# lab8Edit2.net
KiCad netlist of a schematic drawn in EAGLE
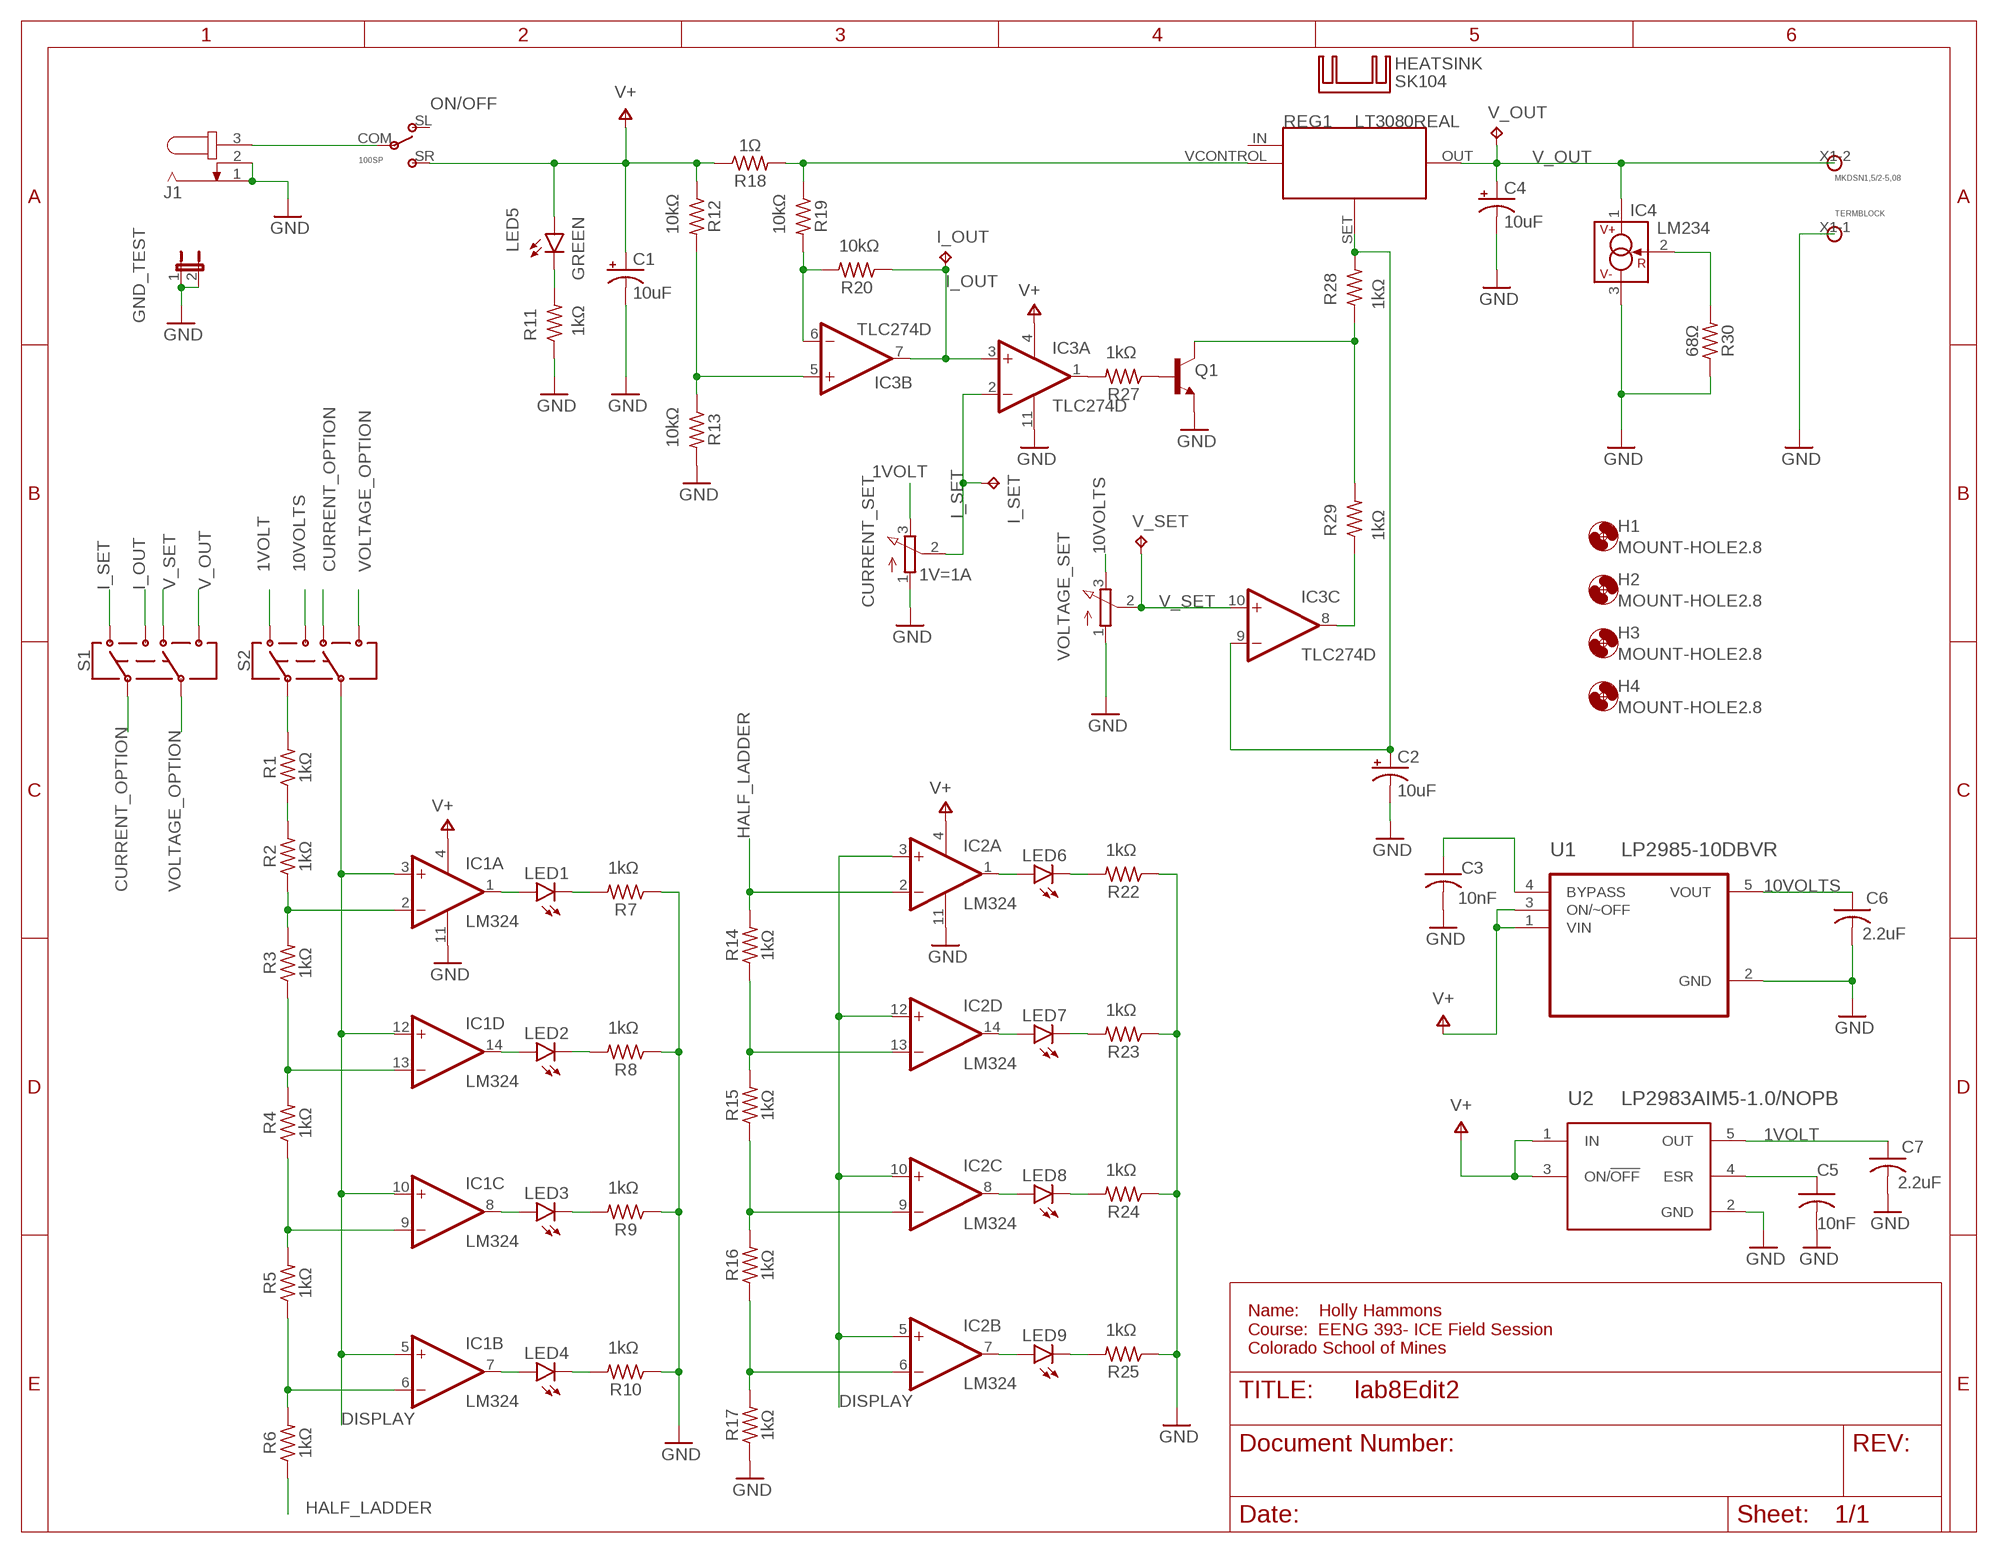
[diagram p0: schematic, sheet 1]

(export (version "E")
  (design (tool "Eeschema 10.0.6"))
  (components
    (comp (ref "C1")
      (value "10uF")
      (footprint "eagle-import:PANASONIC_B")
      (libsource (lib "eagle-import") (part "CPOL-USB"))
    )
    (comp (ref "C2")
      (value "10uF")
      (footprint "eagle-import:PANASONIC_B")
      (libsource (lib "eagle-import") (part "CPOL-USB"))
    )
    (comp (ref "C3")
      (value "10nF")
      (footprint "eagle-import:C1206")
      (libsource (lib "eagle-import") (part "C-USC1206"))
    )
    (comp (ref "C4")
      (value "10uF")
      (footprint "eagle-import:PANASONIC_B")
      (libsource (lib "eagle-import") (part "CPOL-USB"))
    )
    (comp (ref "C5")
      (value "10nF")
      (footprint "eagle-import:C1206")
      (libsource (lib "eagle-import") (part "C-USC1206"))
    )
    (comp (ref "C6")
      (value "2.2uF")
      (footprint "eagle-import:C1206")
      (libsource (lib "eagle-import") (part "C-USC1206"))
    )
    (comp (ref "C7")
      (value "2.2uF")
      (footprint "eagle-import:C1206")
      (libsource (lib "eagle-import") (part "C-USC1206"))
    )
    (comp (ref "CURRENT_SET")
      (value "1V=1A")
      (footprint "eagle-import:EVUF")
      (libsource (lib "eagle-import") (part "EVUAF2"))
    )
    (comp (ref "GND_TEST")
      (value "JP1E")
      (footprint "eagle-import:JP1")
      (libsource (lib "eagle-import") (part "JP1E"))
    )
    (comp (ref "H1")
      (value "MOUNT-HOLE2.8")
      (footprint "eagle-import:2,8")
      (libsource (lib "eagle-import") (part "MOUNT-HOLE2.8"))
    )
    (comp (ref "H2")
      (value "MOUNT-HOLE2.8")
      (footprint "eagle-import:2,8")
      (libsource (lib "eagle-import") (part "MOUNT-HOLE2.8"))
    )
    (comp (ref "H3")
      (value "MOUNT-HOLE2.8")
      (footprint "eagle-import:2,8")
      (libsource (lib "eagle-import") (part "MOUNT-HOLE2.8"))
    )
    (comp (ref "H4")
      (value "MOUNT-HOLE2.8")
      (footprint "eagle-import:2,8")
      (libsource (lib "eagle-import") (part "MOUNT-HOLE2.8"))
    )
    (comp (ref "HEATSINK")
      (value "SK104")
      (footprint "eagle-import:SK104")
      (libsource (lib "eagle-import") (part "SK104"))
    )
    (comp (ref "IC1")
      (value "LM324")
      (footprint "eagle-import:SO14")
      (libsource (lib "eagle-import") (part "LM324D"))
    )
    (comp (ref "IC2")
      (value "LM324")
      (footprint "eagle-import:SO14")
      (libsource (lib "eagle-import") (part "LM324D"))
    )
    (comp (ref "IC3")
      (value "TLC274D")
      (footprint "eagle-import:SO14")
      (libsource (lib "eagle-import") (part "TLC274D"))
    )
    (comp (ref "IC4")
      (value "LM234")
      (footprint "eagle-import:TO92")
      (libsource (lib "eagle-import") (part "LM34Z3"))
    )
    (comp (ref "I_OUT")
      (value "TPPAD1-13")
      (footprint "eagle-import:P1-13")
      (libsource (lib "eagle-import") (part "TPPAD1-13"))
    )
    (comp (ref "I_SET")
      (value "TPPAD1-13")
      (footprint "eagle-import:P1-13")
      (libsource (lib "eagle-import") (part "TPPAD1-13"))
    )
    (comp (ref "J1")
      (value "JACK-PLUG0")
      (footprint "eagle-import:SPC4077")
      (libsource (lib "eagle-import") (part "JACK-PLUG0"))
    )
    (comp (ref "LED1")
      (value "LEDCHIPLED_1206")
      (footprint "eagle-import:CHIPLED_1206")
      (libsource (lib "eagle-import") (part "LEDCHIPLED_1206"))
    )
    (comp (ref "LED2")
      (value "LEDCHIPLED_1206")
      (footprint "eagle-import:CHIPLED_1206")
      (libsource (lib "eagle-import") (part "LEDCHIPLED_1206"))
    )
    (comp (ref "LED3")
      (value "LEDCHIPLED_1206")
      (footprint "eagle-import:CHIPLED_1206")
      (libsource (lib "eagle-import") (part "LEDCHIPLED_1206"))
    )
    (comp (ref "LED4")
      (value "LEDCHIPLED_1206")
      (footprint "eagle-import:CHIPLED_1206")
      (libsource (lib "eagle-import") (part "LEDCHIPLED_1206"))
    )
    (comp (ref "LED5")
      (value "GREEN")
      (footprint "eagle-import:CHIPLED_1206")
      (libsource (lib "eagle-import") (part "LEDCHIPLED_1206"))
    )
    (comp (ref "LED6")
      (value "LEDCHIPLED_1206")
      (footprint "eagle-import:CHIPLED_1206")
      (libsource (lib "eagle-import") (part "LEDCHIPLED_1206"))
    )
    (comp (ref "LED7")
      (value "LEDCHIPLED_1206")
      (footprint "eagle-import:CHIPLED_1206")
      (libsource (lib "eagle-import") (part "LEDCHIPLED_1206"))
    )
    (comp (ref "LED8")
      (value "LEDCHIPLED_1206")
      (footprint "eagle-import:CHIPLED_1206")
      (libsource (lib "eagle-import") (part "LEDCHIPLED_1206"))
    )
    (comp (ref "LED9")
      (value "LEDCHIPLED_1206")
      (footprint "eagle-import:CHIPLED_1206")
      (libsource (lib "eagle-import") (part "LEDCHIPLED_1206"))
    )
    (comp (ref "MKDSN1,5/2-5,08")
      (value "TERMBLOCK")
      (footprint "eagle-import:TERMBLOCK")
      (libsource (lib "eagle-import") (part "TERMBLOCK"))
    )
    (comp (ref "ON/OFF")
      (value "100SP")
      (footprint "eagle-import:SP100")
      (libsource (lib "eagle-import") (part "100SP"))
    )
    (comp (ref "Q1")
      (value "TRANS_NPN-MMBTA42")
      (footprint "eagle-import:SOT23-3")
      (libsource (lib "eagle-import") (part "TRANS_NPN-MMBTA42"))
    )
    (comp (ref "R1")
      (value "1kΩ")
      (footprint "eagle-import:R1206")
      (libsource (lib "eagle-import") (part "R-US_R1206"))
    )
    (comp (ref "R2")
      (value "1kΩ")
      (footprint "eagle-import:R1206")
      (libsource (lib "eagle-import") (part "R-US_R1206"))
    )
    (comp (ref "R3")
      (value "1kΩ")
      (footprint "eagle-import:R1206")
      (libsource (lib "eagle-import") (part "R-US_R1206"))
    )
    (comp (ref "R4")
      (value "1kΩ")
      (footprint "eagle-import:R1206")
      (libsource (lib "eagle-import") (part "R-US_R1206"))
    )
    (comp (ref "R5")
      (value "1kΩ")
      (footprint "eagle-import:R1206")
      (libsource (lib "eagle-import") (part "R-US_R1206"))
    )
    (comp (ref "R6")
      (value "1kΩ")
      (footprint "eagle-import:R1206")
      (libsource (lib "eagle-import") (part "R-US_R1206"))
    )
    (comp (ref "R7")
      (value "1kΩ")
      (footprint "eagle-import:R1206")
      (libsource (lib "eagle-import") (part "R-US_R1206"))
    )
    (comp (ref "R8")
      (value "1kΩ")
      (footprint "eagle-import:R1206")
      (libsource (lib "eagle-import") (part "R-US_R1206"))
    )
    (comp (ref "R9")
      (value "1kΩ")
      (footprint "eagle-import:R1206")
      (libsource (lib "eagle-import") (part "R-US_R1206"))
    )
    (comp (ref "R10")
      (value "1kΩ")
      (footprint "eagle-import:R1206")
      (libsource (lib "eagle-import") (part "R-US_R1206"))
    )
    (comp (ref "R11")
      (value "1kΩ")
      (footprint "eagle-import:R1206")
      (libsource (lib "eagle-import") (part "R-US_R1206"))
    )
    (comp (ref "R12")
      (value "10kΩ")
      (footprint "eagle-import:R1206")
      (libsource (lib "eagle-import") (part "R-US_R1206"))
    )
    (comp (ref "R13")
      (value "10kΩ")
      (footprint "eagle-import:R1206")
      (libsource (lib "eagle-import") (part "R-US_R1206"))
    )
    (comp (ref "R14")
      (value "1kΩ")
      (footprint "eagle-import:R1206")
      (libsource (lib "eagle-import") (part "R-US_R1206"))
    )
    (comp (ref "R15")
      (value "1kΩ")
      (footprint "eagle-import:R1206")
      (libsource (lib "eagle-import") (part "R-US_R1206"))
    )
    (comp (ref "R16")
      (value "1kΩ")
      (footprint "eagle-import:R1206")
      (libsource (lib "eagle-import") (part "R-US_R1206"))
    )
    (comp (ref "R17")
      (value "1kΩ")
      (footprint "eagle-import:R1206")
      (libsource (lib "eagle-import") (part "R-US_R1206"))
    )
    (comp (ref "R18")
      (value "1Ω")
      (footprint "eagle-import:0411_15")
      (libsource (lib "eagle-import") (part "R-US_0411/15"))
    )
    (comp (ref "R19")
      (value "10kΩ")
      (footprint "eagle-import:R1206")
      (libsource (lib "eagle-import") (part "R-US_R1206"))
    )
    (comp (ref "R20")
      (value "10kΩ")
      (footprint "eagle-import:R1206")
      (libsource (lib "eagle-import") (part "R-US_R1206"))
    )
    (comp (ref "R22")
      (value "1kΩ")
      (footprint "eagle-import:R1206")
      (libsource (lib "eagle-import") (part "R-US_R1206"))
    )
    (comp (ref "R23")
      (value "1kΩ")
      (footprint "eagle-import:R1206")
      (libsource (lib "eagle-import") (part "R-US_R1206"))
    )
    (comp (ref "R24")
      (value "1kΩ")
      (footprint "eagle-import:R1206")
      (libsource (lib "eagle-import") (part "R-US_R1206"))
    )
    (comp (ref "R25")
      (value "1kΩ")
      (footprint "eagle-import:R1206")
      (libsource (lib "eagle-import") (part "R-US_R1206"))
    )
    (comp (ref "R27")
      (value "1kΩ")
      (footprint "eagle-import:R1206")
      (libsource (lib "eagle-import") (part "R-US_R1206"))
    )
    (comp (ref "R28")
      (value "1kΩ")
      (footprint "eagle-import:R1206")
      (libsource (lib "eagle-import") (part "R-US_R1206"))
    )
    (comp (ref "R29")
      (value "1kΩ")
      (footprint "eagle-import:R1206")
      (libsource (lib "eagle-import") (part "R-US_R1206"))
    )
    (comp (ref "R30")
      (value "68Ω")
      (footprint "eagle-import:R1206")
      (libsource (lib "eagle-import") (part "R-US_R1206"))
    )
    (comp (ref "REG1")
      (value "LT3080REAL")
      (footprint "eagle-import:LT3080REAL")
      (libsource (lib "eagle-import") (part "LT3080REAL"))
    )
    (comp (ref "S1")
      (value "SWITCH-DPDT-SMD-AYZ0202")
      (footprint "eagle-import:SWITCH_DPDT_SMD_AYZ0202")
      (libsource (lib "eagle-import") (part "SWITCH-DPDT-SMD-AYZ0202"))
    )
    (comp (ref "S2")
      (value "SWITCH-DPDT-SMD-AYZ0202")
      (footprint "eagle-import:SWITCH_DPDT_SMD_AYZ0202")
      (libsource (lib "eagle-import") (part "SWITCH-DPDT-SMD-AYZ0202"))
    )
    (comp (ref "U1")
      (value "LP2985-10DBVR")
      (footprint "eagle-import:SOT95P280X145-5N")
      (fields (field (name "MF") "Texas Instruments"))
      (libsource (lib "eagle-import") (part "LP2985-10DBVR"))
    )
    (comp (ref "U2")
      (value "LP2983AIM5-1.0/NOPB")
      (footprint "eagle-import:SOT95P280X145-5N")
      (fields (field (name "MF") "Texas Instruments"))
      (libsource (lib "eagle-import") (part "LP2983AIM5-1.0/NOPB"))
    )
    (comp (ref "VOLTAGE_SET")
      (value "EVUF2A")
      (footprint "eagle-import:EVUF")
      (libsource (lib "eagle-import") (part "EVUAF2"))
    )
    (comp (ref "V_OUT")
      (value "TPPAD1-13")
      (footprint "eagle-import:P1-13")
      (libsource (lib "eagle-import") (part "TPPAD1-13"))
    )
    (comp (ref "V_SET")
      (value "TPPAD1-13")
      (footprint "eagle-import:P1-13")
      (libsource (lib "eagle-import") (part "TPPAD1-13"))
    )
  )
  (nets
    (net (code "1") (name "/1VOLT") (class "Default")
      (node (ref "C7") (pin "1") (pinfunction "1_1") (pintype "passive"))
      (node (ref "CURRENT_SET") (pin "3") (pinfunction "E_3") (pintype "passive"))
      (node (ref "S2") (pin "3") (pinfunction "3_3") (pintype "bidirectional"))
      (node (ref "U2") (pin "5") (pinfunction "OUT_5") (pintype "output"))
    )
    (net (code "2") (name "/10VOLTS") (class "Default")
      (node (ref "C6") (pin "1") (pinfunction "1_1") (pintype "passive"))
      (node (ref "S2") (pin "1") (pinfunction "1_1") (pintype "bidirectional"))
      (node (ref "U1") (pin "5") (pinfunction "VOUT_5") (pintype "output"))
      (node (ref "VOLTAGE_SET") (pin "3") (pinfunction "E_3") (pintype "passive"))
    )
    (net (code "3") (name "/CURRENT_OPTION") (class "Default")
      (node (ref "S1") (pin "2") (pinfunction "2_2") (pintype "bidirectional"))
      (node (ref "S2") (pin "6") (pinfunction "6_6") (pintype "bidirectional"))
    )
    (net (code "4") (name "/DISPLAY") (class "Default")
      (node (ref "IC1") (pin "10") (pinfunction "+IN_10") (pintype "input"))
      (node (ref "IC1") (pin "12") (pinfunction "+IN_12") (pintype "input"))
      (node (ref "IC1") (pin "3") (pinfunction "+IN_3") (pintype "input"))
      (node (ref "IC1") (pin "5") (pinfunction "+IN_5") (pintype "input"))
      (node (ref "IC2") (pin "10") (pinfunction "+IN_10") (pintype "input"))
      (node (ref "IC2") (pin "12") (pinfunction "+IN_12") (pintype "input"))
      (node (ref "IC2") (pin "3") (pinfunction "+IN_3") (pintype "input"))
      (node (ref "IC2") (pin "5") (pinfunction "+IN_5") (pintype "input"))
      (node (ref "S2") (pin "5") (pinfunction "5_5") (pintype "bidirectional"))
    )
    (net (code "5") (name "/HALF_LADDER") (class "Default")
      (node (ref "IC2") (pin "2") (pinfunction "-IN_2") (pintype "input"))
      (node (ref "R14") (pin "2") (pinfunction "2_2") (pintype "passive"))
      (node (ref "R6") (pin "1") (pinfunction "1_1") (pintype "passive"))
    )
    (net (code "6") (name "/I_OUT") (class "Default")
      (node (ref "IC3") (pin "3") (pinfunction "+IN_3") (pintype "input"))
      (node (ref "IC3") (pin "7") (pinfunction "OUT_7") (pintype "output"))
      (node (ref "I_OUT") (pin "TP") (pinfunction "TP_TP") (pintype "input"))
      (node (ref "R20") (pin "1") (pinfunction "1_1") (pintype "passive"))
      (node (ref "S1") (pin "1") (pinfunction "1_1") (pintype "bidirectional"))
    )
    (net (code "7") (name "/I_SET") (class "Default")
      (node (ref "CURRENT_SET") (pin "2") (pinfunction "S_2") (pintype "passive"))
      (node (ref "IC3") (pin "2") (pinfunction "-IN_2") (pintype "input"))
      (node (ref "I_SET") (pin "TP") (pinfunction "TP_TP") (pintype "input"))
      (node (ref "S1") (pin "3") (pinfunction "3_3") (pintype "bidirectional"))
    )
    (net (code "8") (name "/VOLTAGE_OPTION") (class "Default")
      (node (ref "S1") (pin "5") (pinfunction "5_5") (pintype "bidirectional"))
      (node (ref "S2") (pin "4") (pinfunction "4_4") (pintype "bidirectional"))
    )
    (net (code "9") (name "/V_OUT") (class "Default")
      (node (ref "C4") (pin "+") (pinfunction "+_+") (pintype "passive"))
      (node (ref "IC4") (pin "1") (pinfunction "V+_1") (pintype "passive"))
      (node (ref "MKDSN1,5/2-5,08") (pin "X1-2") (pinfunction "X1-2_X1-2") (pintype "bidirectional"))
      (node (ref "REG1") (pin "OUT") (pinfunction "OUT_OUT") (pintype "bidirectional"))
      (node (ref "S1") (pin "4") (pinfunction "4_4") (pintype "bidirectional"))
      (node (ref "V_OUT") (pin "TP") (pinfunction "TP_TP") (pintype "input"))
    )
    (net (code "10") (name "/V_SET") (class "Default")
      (node (ref "IC3") (pin "10") (pinfunction "+IN_10") (pintype "input"))
      (node (ref "S1") (pin "6") (pinfunction "6_6") (pintype "bidirectional"))
      (node (ref "VOLTAGE_SET") (pin "2") (pinfunction "S_2") (pintype "passive"))
      (node (ref "V_SET") (pin "TP") (pinfunction "TP_TP") (pintype "input"))
    )
    (net (code "11") (name "GND") (class "Default")
      (node (ref "C1") (pin "-") (pinfunction "-_-") (pintype "passive"))
      (node (ref "C2") (pin "-") (pinfunction "-_-") (pintype "passive"))
      (node (ref "C3") (pin "2") (pinfunction "2_2") (pintype "passive"))
      (node (ref "C4") (pin "-") (pinfunction "-_-") (pintype "passive"))
      (node (ref "C5") (pin "2") (pinfunction "2_2") (pintype "passive"))
      (node (ref "C6") (pin "2") (pinfunction "2_2") (pintype "passive"))
      (node (ref "C7") (pin "2") (pinfunction "2_2") (pintype "passive"))
      (node (ref "CURRENT_SET") (pin "1") (pinfunction "A_1") (pintype "passive"))
      (node (ref "GND_TEST") (pin "1") (pinfunction "1_1") (pintype "passive"))
      (node (ref "GND_TEST") (pin "2") (pinfunction "2_2") (pintype "passive"))
      (node (ref "IC1") (pin "11") (pinfunction "V-_11") (pintype "power_in"))
      (node (ref "IC2") (pin "11") (pinfunction "V-_11") (pintype "power_in"))
      (node (ref "IC3") (pin "11") (pinfunction "V-_11") (pintype "power_in"))
      (node (ref "IC4") (pin "3") (pinfunction "V-_3") (pintype "passive"))
      (node (ref "J1") (pin "1") (pinfunction "1_1") (pintype "passive"))
      (node (ref "J1") (pin "2") (pinfunction "2_2") (pintype "passive"))
      (node (ref "MKDSN1,5/2-5,08") (pin "X1-1") (pinfunction "X1-1_X1-1") (pintype "bidirectional"))
      (node (ref "Q1") (pin "2") (pinfunction "E_2") (pintype "passive"))
      (node (ref "R10") (pin "1") (pinfunction "1_1") (pintype "passive"))
      (node (ref "R11") (pin "1") (pinfunction "1_1") (pintype "passive"))
      (node (ref "R13") (pin "2") (pinfunction "2_2") (pintype "passive"))
      (node (ref "R17") (pin "1") (pinfunction "1_1") (pintype "passive"))
      (node (ref "R22") (pin "1") (pinfunction "1_1") (pintype "passive"))
      (node (ref "R23") (pin "1") (pinfunction "1_1") (pintype "passive"))
      (node (ref "R24") (pin "1") (pinfunction "1_1") (pintype "passive"))
      (node (ref "R25") (pin "1") (pinfunction "1_1") (pintype "passive"))
      (node (ref "R30") (pin "1") (pinfunction "1_1") (pintype "passive"))
      (node (ref "R7") (pin "1") (pinfunction "1_1") (pintype "passive"))
      (node (ref "R8") (pin "1") (pinfunction "1_1") (pintype "passive"))
      (node (ref "R9") (pin "1") (pinfunction "1_1") (pintype "passive"))
      (node (ref "U1") (pin "2") (pinfunction "GND_2") (pintype "power_in"))
      (node (ref "U2") (pin "2") (pinfunction "GND_2") (pintype "power_in"))
      (node (ref "VOLTAGE_SET") (pin "1") (pinfunction "A_1") (pintype "passive"))
    )
    (net (code "12") (name "Net-(IC1A--IN)") (class "Default")
      (node (ref "IC1") (pin "2") (pinfunction "-IN_2") (pintype "input"))
      (node (ref "R2") (pin "1") (pinfunction "1_1") (pintype "passive"))
      (node (ref "R3") (pin "2") (pinfunction "2_2") (pintype "passive"))
    )
    (net (code "13") (name "Net-(IC1A-OUT)") (class "Default")
      (node (ref "IC1") (pin "1") (pinfunction "OUT_1") (pintype "output"))
      (node (ref "LED1") (pin "A") (pinfunction "A_A") (pintype "passive"))
    )
    (net (code "14") (name "Net-(IC1B--IN)") (class "Default")
      (node (ref "IC1") (pin "6") (pinfunction "-IN_6") (pintype "input"))
      (node (ref "R5") (pin "1") (pinfunction "1_1") (pintype "passive"))
      (node (ref "R6") (pin "2") (pinfunction "2_2") (pintype "passive"))
    )
    (net (code "15") (name "Net-(IC1B-OUT)") (class "Default")
      (node (ref "IC1") (pin "7") (pinfunction "OUT_7") (pintype "output"))
      (node (ref "LED4") (pin "A") (pinfunction "A_A") (pintype "passive"))
    )
    (net (code "16") (name "Net-(IC1C--IN)") (class "Default")
      (node (ref "IC1") (pin "9") (pinfunction "-IN_9") (pintype "input"))
      (node (ref "R4") (pin "1") (pinfunction "1_1") (pintype "passive"))
      (node (ref "R5") (pin "2") (pinfunction "2_2") (pintype "passive"))
    )
    (net (code "17") (name "Net-(IC1C-OUT)") (class "Default")
      (node (ref "IC1") (pin "8") (pinfunction "OUT_8") (pintype "output"))
      (node (ref "LED3") (pin "A") (pinfunction "A_A") (pintype "passive"))
    )
    (net (code "18") (name "Net-(IC1D--IN)") (class "Default")
      (node (ref "IC1") (pin "13") (pinfunction "-IN_13") (pintype "input"))
      (node (ref "R3") (pin "1") (pinfunction "1_1") (pintype "passive"))
      (node (ref "R4") (pin "2") (pinfunction "2_2") (pintype "passive"))
    )
    (net (code "19") (name "Net-(IC1D-OUT)") (class "Default")
      (node (ref "IC1") (pin "14") (pinfunction "OUT_14") (pintype "output"))
      (node (ref "LED2") (pin "A") (pinfunction "A_A") (pintype "passive"))
    )
    (net (code "20") (name "Net-(IC2A-OUT)") (class "Default")
      (node (ref "IC2") (pin "1") (pinfunction "OUT_1") (pintype "output"))
      (node (ref "LED6") (pin "A") (pinfunction "A_A") (pintype "passive"))
    )
    (net (code "21") (name "Net-(IC2B--IN)") (class "Default")
      (node (ref "IC2") (pin "6") (pinfunction "-IN_6") (pintype "input"))
      (node (ref "R16") (pin "1") (pinfunction "1_1") (pintype "passive"))
      (node (ref "R17") (pin "2") (pinfunction "2_2") (pintype "passive"))
    )
    (net (code "22") (name "Net-(IC2B-OUT)") (class "Default")
      (node (ref "IC2") (pin "7") (pinfunction "OUT_7") (pintype "output"))
      (node (ref "LED9") (pin "A") (pinfunction "A_A") (pintype "passive"))
    )
    (net (code "23") (name "Net-(IC2C--IN)") (class "Default")
      (node (ref "IC2") (pin "9") (pinfunction "-IN_9") (pintype "input"))
      (node (ref "R15") (pin "1") (pinfunction "1_1") (pintype "passive"))
      (node (ref "R16") (pin "2") (pinfunction "2_2") (pintype "passive"))
    )
    (net (code "24") (name "Net-(IC2C-OUT)") (class "Default")
      (node (ref "IC2") (pin "8") (pinfunction "OUT_8") (pintype "output"))
      (node (ref "LED8") (pin "A") (pinfunction "A_A") (pintype "passive"))
    )
    (net (code "25") (name "Net-(IC2D--IN)") (class "Default")
      (node (ref "IC2") (pin "13") (pinfunction "-IN_13") (pintype "input"))
      (node (ref "R14") (pin "1") (pinfunction "1_1") (pintype "passive"))
      (node (ref "R15") (pin "2") (pinfunction "2_2") (pintype "passive"))
    )
    (net (code "26") (name "Net-(IC2D-OUT)") (class "Default")
      (node (ref "IC2") (pin "14") (pinfunction "OUT_14") (pintype "output"))
      (node (ref "LED7") (pin "A") (pinfunction "A_A") (pintype "passive"))
    )
    (net (code "27") (name "Net-(IC3A-OUT)") (class "Default")
      (node (ref "IC3") (pin "1") (pinfunction "OUT_1") (pintype "output"))
      (node (ref "R27") (pin "2") (pinfunction "2_2") (pintype "passive"))
    )
    (net (code "28") (name "Net-(IC3B-+IN)") (class "Default")
      (node (ref "IC3") (pin "5") (pinfunction "+IN_5") (pintype "input"))
      (node (ref "R12") (pin "2") (pinfunction "2_2") (pintype "passive"))
      (node (ref "R13") (pin "1") (pinfunction "1_1") (pintype "passive"))
    )
    (net (code "29") (name "Net-(IC3B--IN)") (class "Default")
      (node (ref "IC3") (pin "6") (pinfunction "-IN_6") (pintype "input"))
      (node (ref "R19") (pin "2") (pinfunction "2_2") (pintype "passive"))
      (node (ref "R20") (pin "2") (pinfunction "2_2") (pintype "passive"))
    )
    (net (code "30") (name "Net-(IC3C--IN)") (class "Default")
      (node (ref "C2") (pin "+") (pinfunction "+_+") (pintype "passive"))
      (node (ref "IC3") (pin "9") (pinfunction "-IN_9") (pintype "input"))
      (node (ref "R28") (pin "2") (pinfunction "2_2") (pintype "passive"))
      (node (ref "REG1") (pin "SET") (pinfunction "SET_SET") (pintype "bidirectional"))
    )
    (net (code "31") (name "Net-(IC3C-OUT)") (class "Default")
      (node (ref "IC3") (pin "8") (pinfunction "OUT_8") (pintype "output"))
      (node (ref "R29") (pin "1") (pinfunction "1_1") (pintype "passive"))
    )
    (net (code "32") (name "Net-(IC4-R)") (class "Default")
      (node (ref "IC4") (pin "2") (pinfunction "R_2") (pintype "passive"))
      (node (ref "R30") (pin "2") (pinfunction "2_2") (pintype "passive"))
    )
    (net (code "33") (name "Net-(J1-Pad3)") (class "Default")
      (node (ref "J1") (pin "3") (pinfunction "3_3") (pintype "passive"))
      (node (ref "ON/OFF") (pin "COM") (pinfunction "COM_COM") (pintype "passive"))
    )
    (net (code "34") (name "Net-(LED1-PadC)") (class "Default")
      (node (ref "LED1") (pin "C") (pinfunction "C_C") (pintype "passive"))
      (node (ref "R7") (pin "2") (pinfunction "2_2") (pintype "passive"))
    )
    (net (code "35") (name "Net-(LED2-PadC)") (class "Default")
      (node (ref "LED2") (pin "C") (pinfunction "C_C") (pintype "passive"))
      (node (ref "R8") (pin "2") (pinfunction "2_2") (pintype "passive"))
    )
    (net (code "36") (name "Net-(LED3-PadC)") (class "Default")
      (node (ref "LED3") (pin "C") (pinfunction "C_C") (pintype "passive"))
      (node (ref "R9") (pin "2") (pinfunction "2_2") (pintype "passive"))
    )
    (net (code "37") (name "Net-(LED4-PadC)") (class "Default")
      (node (ref "LED4") (pin "C") (pinfunction "C_C") (pintype "passive"))
      (node (ref "R10") (pin "2") (pinfunction "2_2") (pintype "passive"))
    )
    (net (code "38") (name "Net-(LED5-PadC)") (class "Default")
      (node (ref "LED5") (pin "C") (pinfunction "C_C") (pintype "passive"))
      (node (ref "R11") (pin "2") (pinfunction "2_2") (pintype "passive"))
    )
    (net (code "39") (name "Net-(LED6-PadC)") (class "Default")
      (node (ref "LED6") (pin "C") (pinfunction "C_C") (pintype "passive"))
      (node (ref "R22") (pin "2") (pinfunction "2_2") (pintype "passive"))
    )
    (net (code "40") (name "Net-(LED7-PadC)") (class "Default")
      (node (ref "LED7") (pin "C") (pinfunction "C_C") (pintype "passive"))
      (node (ref "R23") (pin "2") (pinfunction "2_2") (pintype "passive"))
    )
    (net (code "41") (name "Net-(LED8-PadC)") (class "Default")
      (node (ref "LED8") (pin "C") (pinfunction "C_C") (pintype "passive"))
      (node (ref "R24") (pin "2") (pinfunction "2_2") (pintype "passive"))
    )
    (net (code "42") (name "Net-(LED9-PadC)") (class "Default")
      (node (ref "LED9") (pin "C") (pinfunction "C_C") (pintype "passive"))
      (node (ref "R25") (pin "2") (pinfunction "2_2") (pintype "passive"))
    )
    (net (code "43") (name "Net-(Q1-B)") (class "Default")
      (node (ref "Q1") (pin "1") (pinfunction "B_1") (pintype "passive"))
      (node (ref "R27") (pin "1") (pinfunction "1_1") (pintype "passive"))
    )
    (net (code "44") (name "Net-(Q1-C)") (class "Default")
      (node (ref "Q1") (pin "3") (pinfunction "C_3") (pintype "passive"))
      (node (ref "R28") (pin "1") (pinfunction "1_1") (pintype "passive"))
      (node (ref "R29") (pin "2") (pinfunction "2_2") (pintype "passive"))
    )
    (net (code "45") (name "Net-(R1-Pad1)") (class "Default")
      (node (ref "R1") (pin "1") (pinfunction "1_1") (pintype "passive"))
      (node (ref "R2") (pin "2") (pinfunction "2_2") (pintype "passive"))
    )
    (net (code "46") (name "Net-(R1-Pad2)") (class "Default")
      (node (ref "R1") (pin "2") (pinfunction "2_2") (pintype "passive"))
      (node (ref "S2") (pin "2") (pinfunction "2_2") (pintype "bidirectional"))
    )
    (net (code "47") (name "Net-(REG1-VCTL)") (class "Default")
      (node (ref "R18") (pin "2") (pinfunction "2_2") (pintype "passive"))
      (node (ref "R19") (pin "1") (pinfunction "1_1") (pintype "passive"))
      (node (ref "REG1") (pin "VCONTROL") (pinfunction "VCTL_VCONTROL") (pintype "bidirectional"))
    )
    (net (code "48") (name "Net-(U1-BYPASS)") (class "Default")
      (node (ref "C3") (pin "1") (pinfunction "1_1") (pintype "passive"))
      (node (ref "U1") (pin "4") (pinfunction "BYPASS_4") (pintype "input"))
    )
    (net (code "49") (name "Net-(U2-ESR)") (class "Default")
      (node (ref "C5") (pin "1") (pinfunction "1_1") (pintype "passive"))
      (node (ref "U2") (pin "4") (pinfunction "ESR_4") (pintype "passive"))
    )
    (net (code "50") (name "V+") (class "Default")
      (node (ref "C1") (pin "+") (pinfunction "+_+") (pintype "passive"))
      (node (ref "IC1") (pin "4") (pinfunction "V+_4") (pintype "power_in"))
      (node (ref "IC2") (pin "4") (pinfunction "V+_4") (pintype "power_in"))
      (node (ref "IC3") (pin "4") (pinfunction "V+_4") (pintype "power_in"))
      (node (ref "LED5") (pin "A") (pinfunction "A_A") (pintype "passive"))
      (node (ref "ON/OFF") (pin "SR") (pinfunction "SR_SR") (pintype "passive"))
      (node (ref "R12") (pin "1") (pinfunction "1_1") (pintype "passive"))
      (node (ref "R18") (pin "1") (pinfunction "1_1") (pintype "passive"))
      (node (ref "U1") (pin "1") (pinfunction "VIN_1") (pintype "input"))
      (node (ref "U1") (pin "3") (pinfunction "ON/~{OFF}_3") (pintype "input"))
      (node (ref "U2") (pin "1") (pinfunction "IN_1") (pintype "input"))
      (node (ref "U2") (pin "3") (pinfunction "ON/~{OFF}_3") (pintype "input"))
    )
    (net (code "51") (name "unconnected-(ON/OFF-PadSL)") (class "Default")
      (node (ref "ON/OFF") (pin "SL") (pinfunction "SL_SL") (pintype "passive"))
    )
    (net (code "52") (name "unconnected-(REG1-PadIN)") (class "Default")
      (node (ref "REG1") (pin "IN") (pinfunction "IN_IN") (pintype "bidirectional"))
    )
  )
)
